# untitled.net
KiCad netlist of a schematic drawn in EAGLE
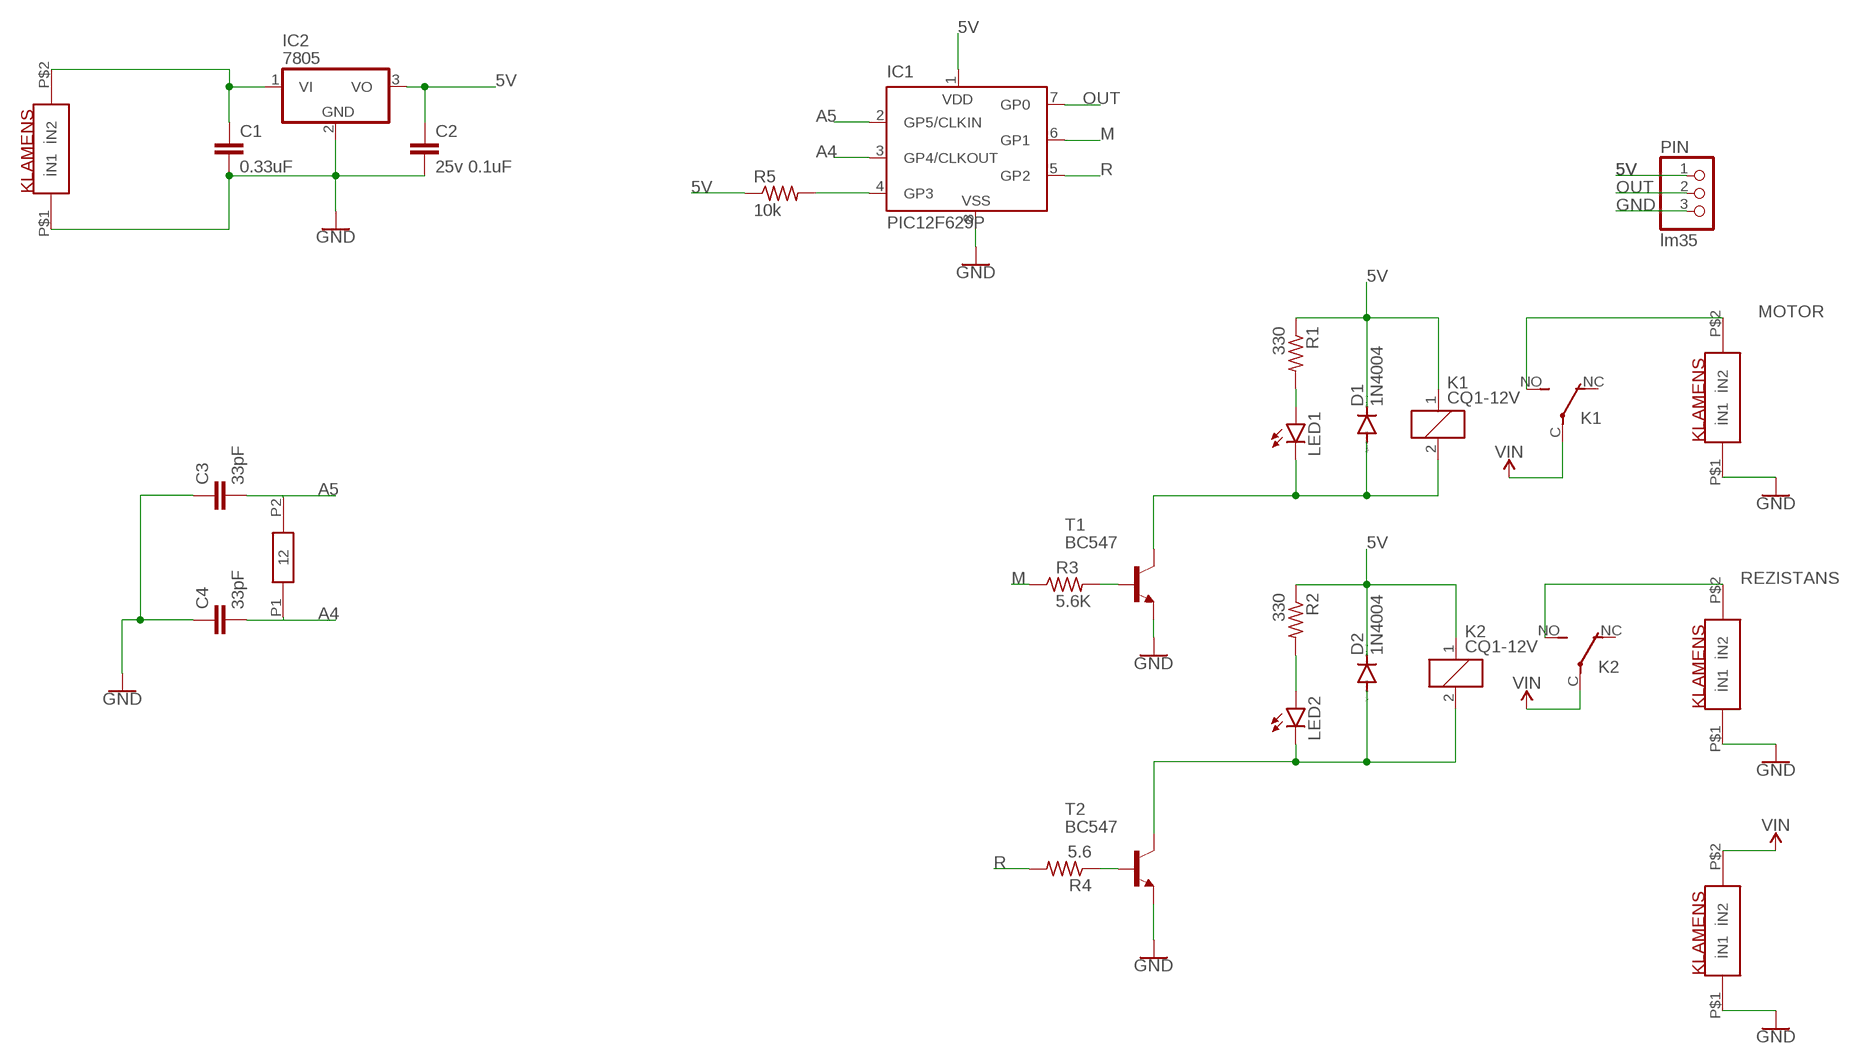
[diagram p0: schematic, sheet 1]

(export (version "E")
  (design (tool "Eeschema 10.0.6"))
  (components
    (comp (ref "C1")
      (value "0.33uF")
      (footprint "eagle-import:C2.5-6")
      (libsource (lib "eagle-import") (part "C2.5/6"))
    )
    (comp (ref "C2")
      (value "25v 0.1uF")
      (footprint "eagle-import:C2.5-6")
      (libsource (lib "eagle-import") (part "C2.5/6"))
    )
    (comp (ref "C3")
      (value "33pF")
      (footprint "eagle-import:C2.5-6")
      (libsource (lib "eagle-import") (part "C2.5/6"))
    )
    (comp (ref "C4")
      (value "33pF")
      (footprint "eagle-import:C2.5-6")
      (libsource (lib "eagle-import") (part "C2.5/6"))
    )
    (comp (ref "D1")
      (value "1N4004")
      (footprint "eagle-import:DO41-10")
      (libsource (lib "eagle-import") (part "1N4004"))
    )
    (comp (ref "D2")
      (value "1N4004")
      (footprint "eagle-import:DO41-10")
      (libsource (lib "eagle-import") (part "1N4004"))
    )
    (comp (ref "IC1")
      (value "PIC12F629P")
      (footprint "eagle-import:DIL8")
      (fields (field (name "MF") "MICROCHIP") (field (name "MPN") "PIC12F629-I/P"))
      (libsource (lib "eagle-import") (part "PIC12F6P29"))
    )
    (comp (ref "IC2")
      (value "7805")
      (footprint "eagle-import:TO220H")
      (libsource (lib "eagle-import") (part "78T08"))
    )
    (comp (ref "K1")
      (value "CQ1-12V")
      (footprint "eagle-import:CQ1")
      (libsource (lib "eagle-import") (part "CQ1-12V"))
    )
    (comp (ref "K2")
      (value "CQ1-12V")
      (footprint "eagle-import:CQ1")
      (libsource (lib "eagle-import") (part "CQ1-12V"))
    )
    (comp (ref "LED1")
      (value "LED3MM")
      (footprint "eagle-import:LED3MM")
      (libsource (lib "eagle-import") (part "LED3MM"))
    )
    (comp (ref "LED2")
      (value "LED3MM")
      (footprint "eagle-import:LED3MM")
      (libsource (lib "eagle-import") (part "LED3MM"))
    )
    (comp (ref "PIN")
      (value "lm35")
      (footprint "eagle-import:1X03")
      (libsource (lib "eagle-import") (part "PINHD-1X3"))
    )
    (comp (ref "R1")
      (value "330")
      (footprint "eagle-import:0207_10")
      (libsource (lib "eagle-import") (part "R-US_0207/10"))
    )
    (comp (ref "R2")
      (value "330")
      (footprint "eagle-import:0207_10")
      (libsource (lib "eagle-import") (part "R-US_0207/10"))
    )
    (comp (ref "R3")
      (value "5.6K")
      (footprint "eagle-import:0207_10")
      (libsource (lib "eagle-import") (part "R-US_0207/10"))
    )
    (comp (ref "R4")
      (value "5.6")
      (footprint "eagle-import:0207_10")
      (libsource (lib "eagle-import") (part "R-US_0207/10"))
    )
    (comp (ref "R5")
      (value "10k")
      (footprint "eagle-import:0207_10")
      (libsource (lib "eagle-import") (part "R-US_0207/10"))
    )
    (comp (ref "T1")
      (value "BC547")
      (footprint "eagle-import:TO92")
      (libsource (lib "eagle-import") (part "BC547"))
    )
    (comp (ref "T2")
      (value "BC547")
      (footprint "eagle-import:TO92")
      (libsource (lib "eagle-import") (part "BC547"))
    )
    (comp (ref "U$1")
      (value "KLAMENS")
      (footprint "eagle-import:KLAMENS")
      (libsource (lib "eagle-import") (part "KLAMENS"))
    )
    (comp (ref "U$2")
      (value "KLAMENS")
      (footprint "eagle-import:KLAMENS")
      (libsource (lib "eagle-import") (part "KLAMENS"))
    )
    (comp (ref "U$3")
      (value "KLAMENS")
      (footprint "eagle-import:KLAMENS")
      (libsource (lib "eagle-import") (part "KLAMENS"))
    )
    (comp (ref "U$5")
      (value "KLAMENS")
      (footprint "eagle-import:KLAMENS")
      (libsource (lib "eagle-import") (part "KLAMENS"))
    )
    (comp (ref "U$6")
      (value "KIRISTAL")
      (footprint "eagle-import:KIRISTAL")
      (libsource (lib "eagle-import") (part "KIRISTAL"))
    )
  )
  (nets
    (net (code "1") (name "/5V") (class "Default")
      (node (ref "C2") (pin "1") (pinfunction "1_1") (pintype "passive"))
      (node (ref "D1") (pin "C") (pinfunction "C_C") (pintype "passive"))
      (node (ref "D2") (pin "C") (pinfunction "C_C") (pintype "passive"))
      (node (ref "IC1") (pin "1") (pinfunction "VDD_1") (pintype "power_in"))
      (node (ref "IC2") (pin "3") (pinfunction "VO_3") (pintype "passive"))
      (node (ref "K1") (pin "1") (pinfunction "1_1") (pintype "passive"))
      (node (ref "K2") (pin "1") (pinfunction "1_1") (pintype "passive"))
      (node (ref "PIN") (pin "1") (pinfunction "1_1") (pintype "passive"))
      (node (ref "R1") (pin "1") (pinfunction "1_1") (pintype "passive"))
      (node (ref "R2") (pin "1") (pinfunction "1_1") (pintype "passive"))
      (node (ref "R5") (pin "1") (pinfunction "1_1") (pintype "passive"))
    )
    (net (code "2") (name "/A4") (class "Default")
      (node (ref "C4") (pin "2") (pinfunction "2_2") (pintype "passive"))
      (node (ref "IC1") (pin "3") (pinfunction "GP4/CLKOUT_3") (pintype "bidirectional"))
      (node (ref "U$6") (pin "P1") (pinfunction "1_P1") (pintype "bidirectional"))
    )
    (net (code "3") (name "/A5") (class "Default")
      (node (ref "C3") (pin "2") (pinfunction "2_2") (pintype "passive"))
      (node (ref "IC1") (pin "2") (pinfunction "GP5/CLKIN_2") (pintype "bidirectional"))
      (node (ref "U$6") (pin "P2") (pinfunction "2_P2") (pintype "bidirectional"))
    )
    (net (code "4") (name "/M") (class "Default")
      (node (ref "IC1") (pin "6") (pinfunction "GP1_6") (pintype "bidirectional"))
      (node (ref "R3") (pin "1") (pinfunction "1_1") (pintype "passive"))
    )
    (net (code "5") (name "/MOTOR") (class "Default")
      (node (ref "K1") (pin "NO") (pinfunction "S_NO") (pintype "passive"))
      (node (ref "U$1") (pin "P$2") (pinfunction "İN2_P$2") (pintype "bidirectional"))
    )
    (net (code "6") (name "/OUT") (class "Default")
      (node (ref "IC1") (pin "7") (pinfunction "GP0_7") (pintype "bidirectional"))
      (node (ref "PIN") (pin "2") (pinfunction "2_2") (pintype "passive"))
    )
    (net (code "7") (name "/R") (class "Default")
      (node (ref "IC1") (pin "5") (pinfunction "GP2_5") (pintype "bidirectional"))
      (node (ref "R4") (pin "2") (pinfunction "2_2") (pintype "passive"))
    )
    (net (code "8") (name "/REZISTANS") (class "Default")
      (node (ref "K2") (pin "NO") (pinfunction "S_NO") (pintype "passive"))
      (node (ref "U$2") (pin "P$2") (pinfunction "İN2_P$2") (pintype "bidirectional"))
    )
    (net (code "9") (name "GND") (class "Default")
      (node (ref "C1") (pin "2") (pinfunction "2_2") (pintype "passive"))
      (node (ref "C2") (pin "2") (pinfunction "2_2") (pintype "passive"))
      (node (ref "C3") (pin "1") (pinfunction "1_1") (pintype "passive"))
      (node (ref "C4") (pin "1") (pinfunction "1_1") (pintype "passive"))
      (node (ref "IC1") (pin "8") (pinfunction "VSS_8") (pintype "power_in"))
      (node (ref "IC2") (pin "2") (pinfunction "GND_2") (pintype "passive"))
      (node (ref "PIN") (pin "3") (pinfunction "3_3") (pintype "passive"))
      (node (ref "T1") (pin "1") (pinfunction "E_1") (pintype "passive"))
      (node (ref "T2") (pin "1") (pinfunction "E_1") (pintype "passive"))
      (node (ref "U$1") (pin "P$1") (pinfunction "İN1_P$1") (pintype "bidirectional"))
      (node (ref "U$2") (pin "P$1") (pinfunction "İN1_P$1") (pintype "bidirectional"))
      (node (ref "U$3") (pin "P$1") (pinfunction "İN1_P$1") (pintype "bidirectional"))
      (node (ref "U$5") (pin "P$1") (pinfunction "İN1_P$1") (pintype "bidirectional"))
    )
    (net (code "10") (name "Net-(IC1-GP3)") (class "Default")
      (node (ref "IC1") (pin "4") (pinfunction "GP3_4") (pintype "input"))
      (node (ref "R5") (pin "2") (pinfunction "2_2") (pintype "passive"))
    )
    (net (code "11") (name "Net-(IC2-VI)") (class "Default")
      (node (ref "C1") (pin "1") (pinfunction "1_1") (pintype "passive"))
      (node (ref "IC2") (pin "1") (pinfunction "VI_1") (pintype "input"))
      (node (ref "U$5") (pin "P$2") (pinfunction "İN2_P$2") (pintype "bidirectional"))
    )
    (net (code "12") (name "Net-(LED1-C)") (class "Default")
      (node (ref "D1") (pin "A") (pinfunction "A_A") (pintype "passive"))
      (node (ref "K1") (pin "2") (pinfunction "2_2") (pintype "passive"))
      (node (ref "LED1") (pin "K") (pinfunction "C_K") (pintype "passive"))
      (node (ref "T1") (pin "3") (pinfunction "C_3") (pintype "passive"))
    )
    (net (code "13") (name "Net-(LED1-PadA)") (class "Default")
      (node (ref "LED1") (pin "A") (pinfunction "A_A") (pintype "passive"))
      (node (ref "R1") (pin "2") (pinfunction "2_2") (pintype "passive"))
    )
    (net (code "14") (name "Net-(LED2-C)") (class "Default")
      (node (ref "D2") (pin "A") (pinfunction "A_A") (pintype "passive"))
      (node (ref "K2") (pin "2") (pinfunction "2_2") (pintype "passive"))
      (node (ref "LED2") (pin "K") (pinfunction "C_K") (pintype "passive"))
      (node (ref "T2") (pin "3") (pinfunction "C_3") (pintype "passive"))
    )
    (net (code "15") (name "Net-(LED2-PadA)") (class "Default")
      (node (ref "LED2") (pin "A") (pinfunction "A_A") (pintype "passive"))
      (node (ref "R2") (pin "2") (pinfunction "2_2") (pintype "passive"))
    )
    (net (code "16") (name "Net-(T1-B)") (class "Default")
      (node (ref "R3") (pin "2") (pinfunction "2_2") (pintype "passive"))
      (node (ref "T1") (pin "2") (pinfunction "B_2") (pintype "passive"))
    )
    (net (code "17") (name "Net-(T2-B)") (class "Default")
      (node (ref "R4") (pin "1") (pinfunction "1_1") (pintype "passive"))
      (node (ref "T2") (pin "2") (pinfunction "B_2") (pintype "passive"))
    )
    (net (code "18") (name "VIN") (class "Default")
      (node (ref "K1") (pin "C") (pinfunction "P_C") (pintype "passive"))
      (node (ref "K2") (pin "C") (pinfunction "P_C") (pintype "passive"))
      (node (ref "U$3") (pin "P$2") (pinfunction "İN2_P$2") (pintype "bidirectional"))
    )
    (net (code "19") (name "unconnected-(K1B-O-PadNC)") (class "Default")
      (node (ref "K1") (pin "NC") (pinfunction "O_NC") (pintype "passive"))
    )
    (net (code "20") (name "unconnected-(K2B-O-PadNC)") (class "Default")
      (node (ref "K2") (pin "NC") (pinfunction "O_NC") (pintype "passive"))
    )
  )
)
